# module-v3.net
KiCad netlist of a schematic drawn in EAGLE
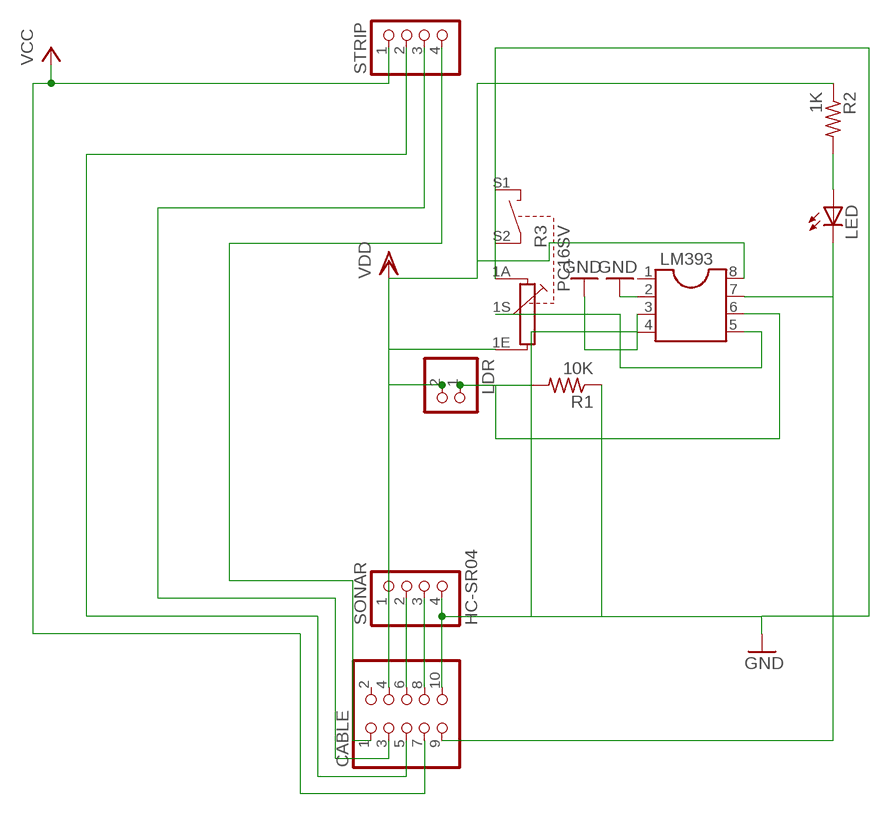
[diagram p0: schematic, sheet 1]

(export (version "E")
  (design (tool "Eeschema 10.0.6"))
  (components
    (comp (ref "CABLE")
      (value "PINHD-2X5")
      (footprint "eagle-import:2X05")
      (libsource (lib "eagle-import") (part "PINHD-2X5"))
    )
    (comp (ref "LDR")
      (value "PINHD-1X2-DAIOGO")
      (footprint "eagle-import:1X02")
      (libsource (lib "eagle-import") (part "PINHD-1X2-DAIOGO"))
    )
    (comp (ref "LED")
      (value "LED3MM")
      (footprint "eagle-import:LED3MM")
      (libsource (lib "eagle-import") (part "LED3MM"))
    )
    (comp (ref "LM393")
      (value "DIL8")
      (footprint "eagle-import:DIL08")
      (libsource (lib "eagle-import") (part "DIL8"))
    )
    (comp (ref "R1")
      (value "10K")
      (footprint "eagle-import:0207_10")
      (libsource (lib "eagle-import") (part "R-US_0207/10"))
    )
    (comp (ref "R2")
      (value "1K")
      (footprint "eagle-import:0207_10")
      (libsource (lib "eagle-import") (part "R-US_0207/10"))
    )
    (comp (ref "R3")
      (value "PC16SV")
      (footprint "eagle-import:PC16SV")
      (libsource (lib "eagle-import") (part "PC16SV"))
    )
    (comp (ref "SONAR")
      (value "HC-SR04")
      (footprint "eagle-import:1X04")
      (libsource (lib "eagle-import") (part "PINHD-1X4"))
    )
    (comp (ref "STRIP")
      (value "PINHD-1X4")
      (footprint "eagle-import:1X04")
      (libsource (lib "eagle-import") (part "PINHD-1X4"))
    )
  )
  (nets
    (net (code "1") (name "GND") (class "Default")
      (node (ref "CABLE") (pin "10") (pinfunction "10_10") (pintype "passive"))
      (node (ref "LM393") (pin "2") (pinfunction "2_2") (pintype "passive"))
      (node (ref "LM393") (pin "3") (pinfunction "3_3") (pintype "passive"))
      (node (ref "LM393") (pin "4") (pinfunction "4_4") (pintype "passive"))
      (node (ref "R1") (pin "1") (pinfunction "1_1") (pintype "passive"))
      (node (ref "R3") (pin "1A") (pinfunction "1A_1A") (pintype "passive"))
      (node (ref "SONAR") (pin "4") (pinfunction "4_4") (pintype "passive"))
    )
    (net (code "2") (name "Net-(CABLE-Pad1)") (class "Default")
      (node (ref "CABLE") (pin "1") (pinfunction "1_1") (pintype "passive"))
      (node (ref "STRIP") (pin "4") (pinfunction "4_4") (pintype "passive"))
    )
    (net (code "3") (name "Net-(CABLE-Pad3)") (class "Default")
      (node (ref "CABLE") (pin "3") (pinfunction "3_3") (pintype "passive"))
      (node (ref "STRIP") (pin "3") (pinfunction "3_3") (pintype "passive"))
    )
    (net (code "4") (name "Net-(CABLE-Pad5)") (class "Default")
      (node (ref "CABLE") (pin "5") (pinfunction "5_5") (pintype "passive"))
      (node (ref "STRIP") (pin "2") (pinfunction "2_2") (pintype "passive"))
    )
    (net (code "5") (name "Net-(CABLE-Pad6)") (class "Default")
      (node (ref "CABLE") (pin "6") (pinfunction "6_6") (pintype "passive"))
      (node (ref "SONAR") (pin "2") (pinfunction "2_2") (pintype "passive"))
    )
    (net (code "6") (name "Net-(CABLE-Pad8)") (class "Default")
      (node (ref "CABLE") (pin "8") (pinfunction "8_8") (pintype "passive"))
      (node (ref "SONAR") (pin "3") (pinfunction "3_3") (pintype "passive"))
    )
    (net (code "7") (name "Net-(LDR-Pad1)") (class "Default")
      (node (ref "LDR") (pin "1") (pinfunction "1_1") (pintype "passive"))
      (node (ref "LM393") (pin "6") (pinfunction "6_6") (pintype "passive"))
      (node (ref "R1") (pin "2") (pinfunction "2_2") (pintype "passive"))
    )
    (net (code "8") (name "Net-(LED-C)") (class "Default")
      (node (ref "CABLE") (pin "9") (pinfunction "9_9") (pintype "passive"))
      (node (ref "LED") (pin "K") (pinfunction "C_K") (pintype "passive"))
      (node (ref "LM393") (pin "7") (pinfunction "7_7") (pintype "passive"))
    )
    (net (code "9") (name "Net-(LED-PadA)") (class "Default")
      (node (ref "LED") (pin "A") (pinfunction "A_A") (pintype "passive"))
      (node (ref "R2") (pin "2") (pinfunction "2_2") (pintype "passive"))
    )
    (net (code "10") (name "Net-(LM393-Pad5)") (class "Default")
      (node (ref "LM393") (pin "5") (pinfunction "5_5") (pintype "passive"))
      (node (ref "R3") (pin "1S") (pinfunction "1S_1S") (pintype "passive"))
    )
    (net (code "11") (name "VCC") (class "Default")
      (node (ref "CABLE") (pin "7") (pinfunction "7_7") (pintype "passive"))
      (node (ref "STRIP") (pin "1") (pinfunction "1_1") (pintype "passive"))
    )
    (net (code "12") (name "VDD") (class "Default")
      (node (ref "CABLE") (pin "4") (pinfunction "4_4") (pintype "passive"))
      (node (ref "LDR") (pin "2") (pinfunction "2_2") (pintype "passive"))
      (node (ref "LM393") (pin "8") (pinfunction "8_8") (pintype "passive"))
      (node (ref "R2") (pin "1") (pinfunction "1_1") (pintype "passive"))
      (node (ref "R3") (pin "1E") (pinfunction "1E_1E") (pintype "passive"))
      (node (ref "SONAR") (pin "1") (pinfunction "1_1") (pintype "passive"))
    )
    (net (code "13") (name "unconnected-(CABLE-Pad2)") (class "Default")
      (node (ref "CABLE") (pin "2") (pinfunction "2_2") (pintype "passive"))
    )
    (net (code "14") (name "unconnected-(LM393-Pad1)") (class "Default")
      (node (ref "LM393") (pin "1") (pinfunction "1_1") (pintype "passive"))
    )
    (net (code "15") (name "unconnected-(R3-PadS1)") (class "Default")
      (node (ref "R3") (pin "S1") (pinfunction "S1_S1") (pintype "passive"))
    )
    (net (code "16") (name "unconnected-(R3-PadS2)") (class "Default")
      (node (ref "R3") (pin "S2") (pinfunction "S2_S2") (pintype "passive"))
    )
  )
)
